# MotorModule.net
KiCad netlist of a schematic drawn in EAGLE
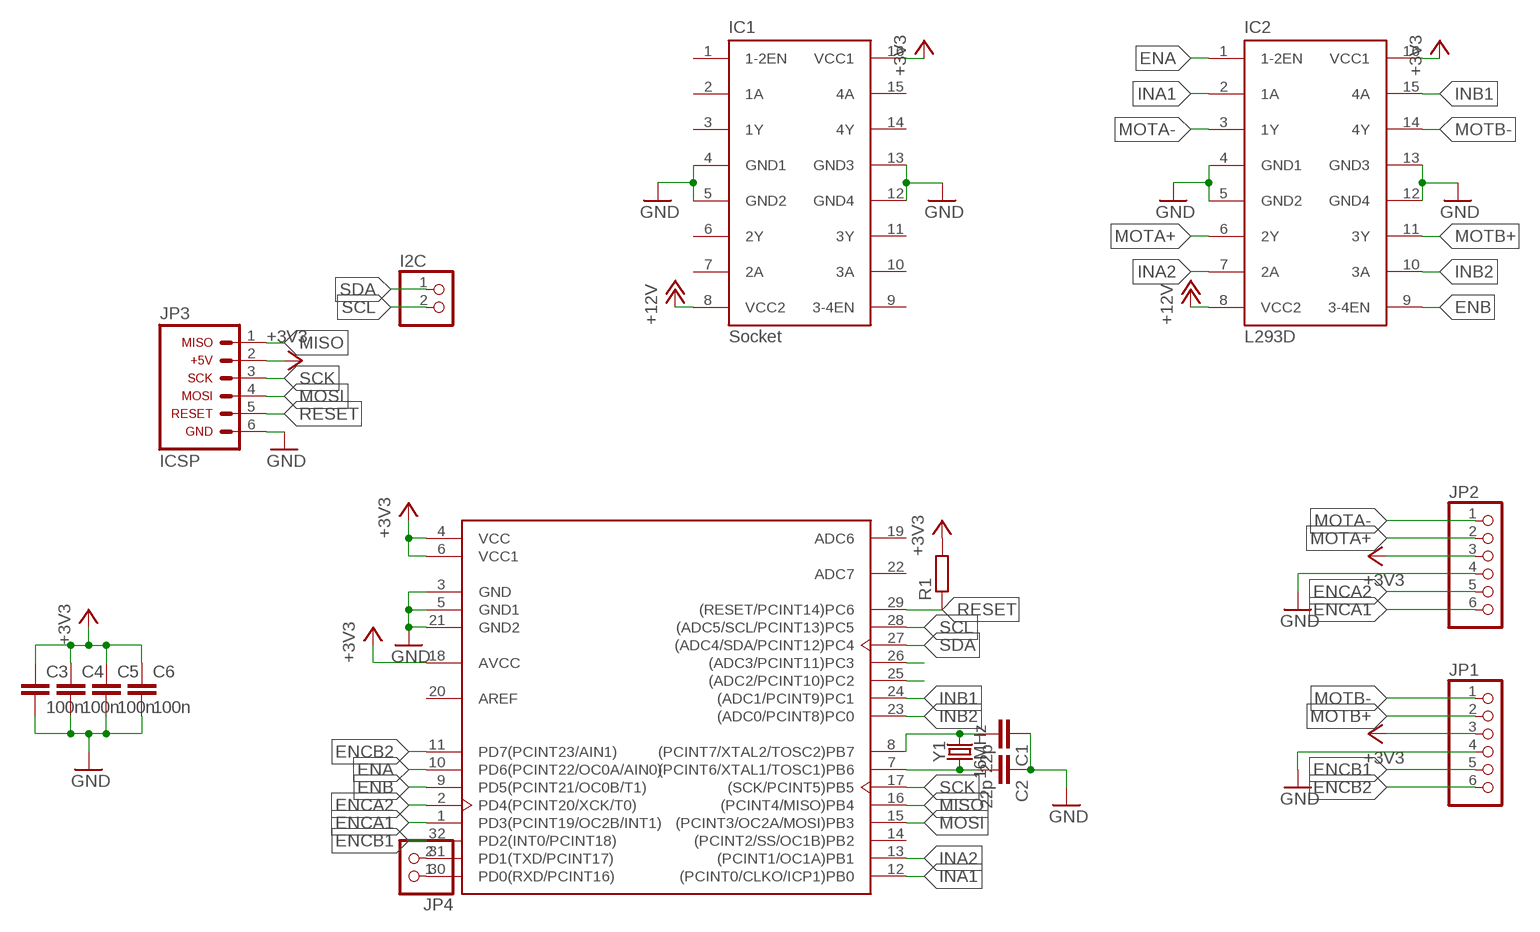
[diagram p0: schematic, sheet 1]

(export (version "E")
  (design (tool "Eeschema 10.0.6"))
  (components
    (comp (ref "C1")
      (value "22p")
      (footprint "eagle-import:C1206")
      (libsource (lib "eagle-import") (part "C-EUC1206"))
    )
    (comp (ref "C2")
      (value "22p")
      (footprint "eagle-import:C1206")
      (libsource (lib "eagle-import") (part "C-EUC1206"))
    )
    (comp (ref "C3")
      (value "100n")
      (footprint "eagle-import:C1206")
      (libsource (lib "eagle-import") (part "C-EUC1206"))
    )
    (comp (ref "C4")
      (value "100n")
      (footprint "eagle-import:C1206")
      (libsource (lib "eagle-import") (part "C-EUC1206"))
    )
    (comp (ref "C5")
      (value "100n")
      (footprint "eagle-import:C1206")
      (libsource (lib "eagle-import") (part "C-EUC1206"))
    )
    (comp (ref "C6")
      (value "100n")
      (footprint "eagle-import:C1206")
      (libsource (lib "eagle-import") (part "C-EUC1206"))
    )
    (comp (ref "I2C")
      (value "PINHD-1X2")
      (footprint "eagle-import:1X02")
      (libsource (lib "eagle-import") (part "PINHD-1X2"))
    )
    (comp (ref "IC1")
      (value "Socket")
      (footprint "eagle-import:L293")
      (fields (field (name "MPN") "L293D"))
      (libsource (lib "eagle-import") (part "L293D"))
    )
    (comp (ref "IC2")
      (value "L293D")
      (footprint "eagle-import:L293")
      (libsource (lib "eagle-import") (part "L293D"))
    )
    (comp (ref "JP1")
      (value "PINHD-1X6/90")
      (footprint "eagle-import:1X06_90")
      (libsource (lib "eagle-import") (part "PINHD-1X6/90"))
    )
    (comp (ref "JP2")
      (value "PINHD-1X6/90")
      (footprint "eagle-import:1X06_90")
      (libsource (lib "eagle-import") (part "PINHD-1X6/90"))
    )
    (comp (ref "JP3")
      (value "ICSP_HEADER")
      (footprint "eagle-import:ICSP_HEADER")
      (libsource (lib "eagle-import") (part "ICSP_HEADER"))
    )
    (comp (ref "JP4")
      (value "PINHD-1X2")
      (footprint "eagle-import:1X02")
      (libsource (lib "eagle-import") (part "PINHD-1X2"))
    )
    (comp (ref "R1")
      (value "R-EU_M1206")
      (footprint "eagle-import:M1206")
      (libsource (lib "eagle-import") (part "R-EU_M1206"))
    )
    (comp (ref "U1")
      (value "ATMEGA328P-AU")
      (footprint "eagle-import:TQFP-32")
      (fields
        (field (name "DIGIKEY_PART_NUMBER") "ATMEGA328P-AU-ND")
        (field (name "MANUFACTURER") "Microchip Technology")
        (field (name "CREATED_BY") "PCBLayout.com")
      )
      (libsource (lib "eagle-import") (part "ATMEGA328P-AU"))
    )
    (comp (ref "Y1")
      (value "16MHz")
      (footprint "eagle-import:CRYSTAL-SMD-5X3.2-4PAD")
      (libsource (lib "eagle-import") (part "CRYSTAL-16MHZSMD-5X3.2"))
    )
  )
  (nets
    (net (code "1") (name "+3V3") (class "Default")
      (node (ref "C3") (pin "1") (pinfunction "1_1") (pintype "passive"))
      (node (ref "C4") (pin "1") (pinfunction "1_1") (pintype "passive"))
      (node (ref "C5") (pin "1") (pinfunction "1_1") (pintype "passive"))
      (node (ref "C6") (pin "1") (pinfunction "1_1") (pintype "passive"))
      (node (ref "IC1") (pin "16") (pinfunction "VCC1_16") (pintype "power_in"))
      (node (ref "IC2") (pin "16") (pinfunction "VCC1_16") (pintype "power_in"))
      (node (ref "JP1") (pin "3") (pinfunction "3_3") (pintype "passive"))
      (node (ref "JP2") (pin "3") (pinfunction "3_3") (pintype "passive"))
      (node (ref "JP3") (pin "2") (pinfunction "2_2") (pintype "passive"))
      (node (ref "R1") (pin "2") (pinfunction "2_2") (pintype "passive"))
      (node (ref "U1") (pin "18") (pinfunction "AVCC_18") (pintype "power_in"))
      (node (ref "U1") (pin "4") (pinfunction "VCC_4") (pintype "power_in"))
      (node (ref "U1") (pin "6") (pinfunction "VCC1_6") (pintype "power_in"))
    )
    (net (code "2") (name "+12V") (class "Default")
      (node (ref "IC1") (pin "8") (pinfunction "VCC2_8") (pintype "power_in"))
      (node (ref "IC2") (pin "8") (pinfunction "VCC2_8") (pintype "power_in"))
    )
    (net (code "3") (name "/AREF") (class "Default")
      (node (ref "U1") (pin "20") (pinfunction "AREF_20") (pintype "power_in"))
    )
    (net (code "4") (name "ENA") (class "Default")
      (node (ref "IC2") (pin "1") (pinfunction "1-2EN_1") (pintype "input"))
      (node (ref "U1") (pin "10") (pinfunction "PD6(PCINT22/OC0A/AIN0)_10") (pintype "bidirectional"))
    )
    (net (code "5") (name "ENB") (class "Default")
      (node (ref "IC2") (pin "9") (pinfunction "3-4EN_9") (pintype "input"))
      (node (ref "U1") (pin "9") (pinfunction "PD5(PCINT21/OC0B/T1)_9") (pintype "bidirectional"))
    )
    (net (code "6") (name "ENCA1") (class "Default")
      (node (ref "JP2") (pin "6") (pinfunction "6_6") (pintype "passive"))
      (node (ref "U1") (pin "1") (pinfunction "PD3(PCINT19/OC2B/INT1)_1") (pintype "bidirectional"))
    )
    (net (code "7") (name "ENCA2") (class "Default")
      (node (ref "JP2") (pin "5") (pinfunction "5_5") (pintype "passive"))
      (node (ref "U1") (pin "2") (pinfunction "PD4(PCINT20/XCK/T0)_2") (pintype "bidirectional"))
    )
    (net (code "8") (name "ENCB1") (class "Default")
      (node (ref "JP1") (pin "5") (pinfunction "5_5") (pintype "passive"))
      (node (ref "U1") (pin "32") (pinfunction "PD2(INT0/PCINT18)_32") (pintype "bidirectional"))
    )
    (net (code "9") (name "ENCB2") (class "Default")
      (node (ref "JP1") (pin "6") (pinfunction "6_6") (pintype "passive"))
      (node (ref "U1") (pin "11") (pinfunction "PD7(PCINT23/AIN1)_11") (pintype "bidirectional"))
    )
    (net (code "10") (name "GND") (class "Default")
      (node (ref "C1") (pin "1") (pinfunction "1_1") (pintype "passive"))
      (node (ref "C2") (pin "1") (pinfunction "1_1") (pintype "passive"))
      (node (ref "C3") (pin "2") (pinfunction "2_2") (pintype "passive"))
      (node (ref "C4") (pin "2") (pinfunction "2_2") (pintype "passive"))
      (node (ref "C5") (pin "2") (pinfunction "2_2") (pintype "passive"))
      (node (ref "C6") (pin "2") (pinfunction "2_2") (pintype "passive"))
      (node (ref "IC1") (pin "12") (pinfunction "GND4_12") (pintype "power_in"))
      (node (ref "IC1") (pin "13") (pinfunction "GND3_13") (pintype "power_in"))
      (node (ref "IC1") (pin "4") (pinfunction "GND1_4") (pintype "power_in"))
      (node (ref "IC1") (pin "5") (pinfunction "GND2_5") (pintype "power_in"))
      (node (ref "IC2") (pin "12") (pinfunction "GND4_12") (pintype "power_in"))
      (node (ref "IC2") (pin "13") (pinfunction "GND3_13") (pintype "power_in"))
      (node (ref "IC2") (pin "4") (pinfunction "GND1_4") (pintype "power_in"))
      (node (ref "IC2") (pin "5") (pinfunction "GND2_5") (pintype "power_in"))
      (node (ref "JP1") (pin "4") (pinfunction "4_4") (pintype "passive"))
      (node (ref "JP2") (pin "4") (pinfunction "4_4") (pintype "passive"))
      (node (ref "JP3") (pin "6") (pinfunction "6_6") (pintype "passive"))
      (node (ref "U1") (pin "21") (pinfunction "GND2_21") (pintype "power_in"))
      (node (ref "U1") (pin "3") (pinfunction "GND_3") (pintype "power_in"))
      (node (ref "U1") (pin "5") (pinfunction "GND1_5") (pintype "power_in"))
    )
    (net (code "11") (name "INA1") (class "Default")
      (node (ref "IC2") (pin "2") (pinfunction "1A_2") (pintype "input"))
      (node (ref "U1") (pin "12") (pinfunction "(PCINT0/CLKO/ICP1)PB0_12") (pintype "bidirectional"))
    )
    (net (code "12") (name "INA2") (class "Default")
      (node (ref "IC2") (pin "7") (pinfunction "2A_7") (pintype "input"))
      (node (ref "U1") (pin "13") (pinfunction "(PCINT1/OC1A)PB1_13") (pintype "bidirectional"))
    )
    (net (code "13") (name "INB1") (class "Default")
      (node (ref "IC2") (pin "15") (pinfunction "4A_15") (pintype "input"))
      (node (ref "U1") (pin "24") (pinfunction "(ADC1/PCINT9)PC1_24") (pintype "bidirectional"))
    )
    (net (code "14") (name "INB2") (class "Default")
      (node (ref "IC2") (pin "10") (pinfunction "3A_10") (pintype "input"))
      (node (ref "U1") (pin "23") (pinfunction "(ADC0/PCINT8)PC0_23") (pintype "bidirectional"))
    )
    (net (code "15") (name "MISO") (class "Default")
      (node (ref "JP3") (pin "1") (pinfunction "1_1") (pintype "passive"))
      (node (ref "U1") (pin "16") (pinfunction "(PCINT4/MISO)PB4_16") (pintype "bidirectional"))
    )
    (net (code "16") (name "MOSI") (class "Default")
      (node (ref "JP3") (pin "4") (pinfunction "4_4") (pintype "passive"))
      (node (ref "U1") (pin "15") (pinfunction "(PCINT3/OC2A/MOSI)PB3_15") (pintype "bidirectional"))
    )
    (net (code "17") (name "MOTA+") (class "Default")
      (node (ref "IC2") (pin "6") (pinfunction "2Y_6") (pintype "output"))
      (node (ref "JP2") (pin "2") (pinfunction "2_2") (pintype "passive"))
    )
    (net (code "18") (name "MOTA-") (class "Default")
      (node (ref "IC2") (pin "3") (pinfunction "1Y_3") (pintype "output"))
      (node (ref "JP2") (pin "1") (pinfunction "1_1") (pintype "passive"))
    )
    (net (code "19") (name "MOTB+") (class "Default")
      (node (ref "IC2") (pin "11") (pinfunction "3Y_11") (pintype "output"))
      (node (ref "JP1") (pin "2") (pinfunction "2_2") (pintype "passive"))
    )
    (net (code "20") (name "MOTB-") (class "Default")
      (node (ref "IC2") (pin "14") (pinfunction "4Y_14") (pintype "output"))
      (node (ref "JP1") (pin "1") (pinfunction "1_1") (pintype "passive"))
    )
    (net (code "21") (name "Net-(U1-(PCINT6{slash}XTAL1{slash}TOSC1)PB6)") (class "Default")
      (node (ref "C2") (pin "2") (pinfunction "2_2") (pintype "passive"))
      (node (ref "U1") (pin "7") (pinfunction "(PCINT6/XTAL1/TOSC1)PB6_7") (pintype "bidirectional"))
      (node (ref "Y1") (pin "1") (pinfunction "1_1") (pintype "passive"))
    )
    (net (code "22") (name "Net-(U1-(PCINT7{slash}XTAL2{slash}TOSC2)PB7)") (class "Default")
      (node (ref "C1") (pin "2") (pinfunction "2_2") (pintype "passive"))
      (node (ref "U1") (pin "8") (pinfunction "(PCINT7/XTAL2/TOSC2)PB7_8") (pintype "bidirectional"))
      (node (ref "Y1") (pin "3") (pinfunction "2_3") (pintype "passive"))
    )
    (net (code "23") (name "Net-(U1-PD0(RXD{slash}PCINT16))") (class "Default")
      (node (ref "JP4") (pin "1") (pinfunction "1_1") (pintype "passive"))
      (node (ref "U1") (pin "30") (pinfunction "PD0(RXD/PCINT16)_30") (pintype "bidirectional"))
    )
    (net (code "24") (name "Net-(U1-PD1(TXD{slash}PCINT17))") (class "Default")
      (node (ref "JP4") (pin "2") (pinfunction "2_2") (pintype "passive"))
      (node (ref "U1") (pin "31") (pinfunction "PD1(TXD/PCINT17)_31") (pintype "bidirectional"))
    )
    (net (code "25") (name "RESET") (class "Default")
      (node (ref "JP3") (pin "5") (pinfunction "5_5") (pintype "passive"))
      (node (ref "R1") (pin "1") (pinfunction "1_1") (pintype "passive"))
      (node (ref "U1") (pin "29") (pinfunction "(RESET/PCINT14)PC6_29") (pintype "bidirectional"))
    )
    (net (code "26") (name "SCK") (class "Default")
      (node (ref "JP3") (pin "3") (pinfunction "3_3") (pintype "passive"))
      (node (ref "U1") (pin "17") (pinfunction "(SCK/PCINT5)PB5_17") (pintype "bidirectional"))
    )
    (net (code "27") (name "SCL") (class "Default")
      (node (ref "I2C") (pin "2") (pinfunction "2_2") (pintype "passive"))
      (node (ref "U1") (pin "28") (pinfunction "(ADC5/SCL/PCINT13)PC5_28") (pintype "bidirectional"))
    )
    (net (code "28") (name "SDA") (class "Default")
      (node (ref "I2C") (pin "1") (pinfunction "1_1") (pintype "passive"))
      (node (ref "U1") (pin "27") (pinfunction "(ADC4/SDA/PCINT12)PC4_27") (pintype "bidirectional"))
    )
    (net (code "29") (name "unconnected-(IC1-1-2EN-Pad1)") (class "Default")
      (node (ref "IC1") (pin "1") (pinfunction "1-2EN_1") (pintype "input"))
    )
    (net (code "30") (name "unconnected-(IC1-1A-Pad2)") (class "Default")
      (node (ref "IC1") (pin "2") (pinfunction "1A_2") (pintype "input"))
    )
    (net (code "31") (name "unconnected-(IC1-1Y-Pad3)") (class "Default")
      (node (ref "IC1") (pin "3") (pinfunction "1Y_3") (pintype "output"))
    )
    (net (code "32") (name "unconnected-(IC1-2A-Pad7)") (class "Default")
      (node (ref "IC1") (pin "7") (pinfunction "2A_7") (pintype "input"))
    )
    (net (code "33") (name "unconnected-(IC1-2Y-Pad6)") (class "Default")
      (node (ref "IC1") (pin "6") (pinfunction "2Y_6") (pintype "output"))
    )
    (net (code "34") (name "unconnected-(IC1-3-4EN-Pad9)") (class "Default")
      (node (ref "IC1") (pin "9") (pinfunction "3-4EN_9") (pintype "input"))
    )
    (net (code "35") (name "unconnected-(IC1-3A-Pad10)") (class "Default")
      (node (ref "IC1") (pin "10") (pinfunction "3A_10") (pintype "input"))
    )
    (net (code "36") (name "unconnected-(IC1-3Y-Pad11)") (class "Default")
      (node (ref "IC1") (pin "11") (pinfunction "3Y_11") (pintype "output"))
    )
    (net (code "37") (name "unconnected-(IC1-4A-Pad15)") (class "Default")
      (node (ref "IC1") (pin "15") (pinfunction "4A_15") (pintype "input"))
    )
    (net (code "38") (name "unconnected-(IC1-4Y-Pad14)") (class "Default")
      (node (ref "IC1") (pin "14") (pinfunction "4Y_14") (pintype "output"))
    )
    (net (code "39") (name "unconnected-(U1-(ADC2{slash}PCINT10)PC2-Pad25)") (class "Default")
      (node (ref "U1") (pin "25") (pinfunction "(ADC2/PCINT10)PC2_25") (pintype "bidirectional"))
    )
    (net (code "40") (name "unconnected-(U1-(ADC3{slash}PCINT11)PC3-Pad26)") (class "Default")
      (node (ref "U1") (pin "26") (pinfunction "(ADC3/PCINT11)PC3_26") (pintype "bidirectional"))
    )
    (net (code "41") (name "unconnected-(U1-(PCINT2{slash}SS{slash}OC1B)PB2-Pad14)") (class "Default")
      (node (ref "U1") (pin "14") (pinfunction "(PCINT2/SS/OC1B)PB2_14") (pintype "bidirectional"))
    )
    (net (code "42") (name "unconnected-(U1-ADC6-Pad19)") (class "Default")
      (node (ref "U1") (pin "19") (pinfunction "ADC6_19") (pintype "input"))
    )
    (net (code "43") (name "unconnected-(U1-ADC7-Pad22)") (class "Default")
      (node (ref "U1") (pin "22") (pinfunction "ADC7_22") (pintype "input"))
    )
  )
)
